# Sheet1.net
KiCad netlist of a schematic drawn in Altium Designer
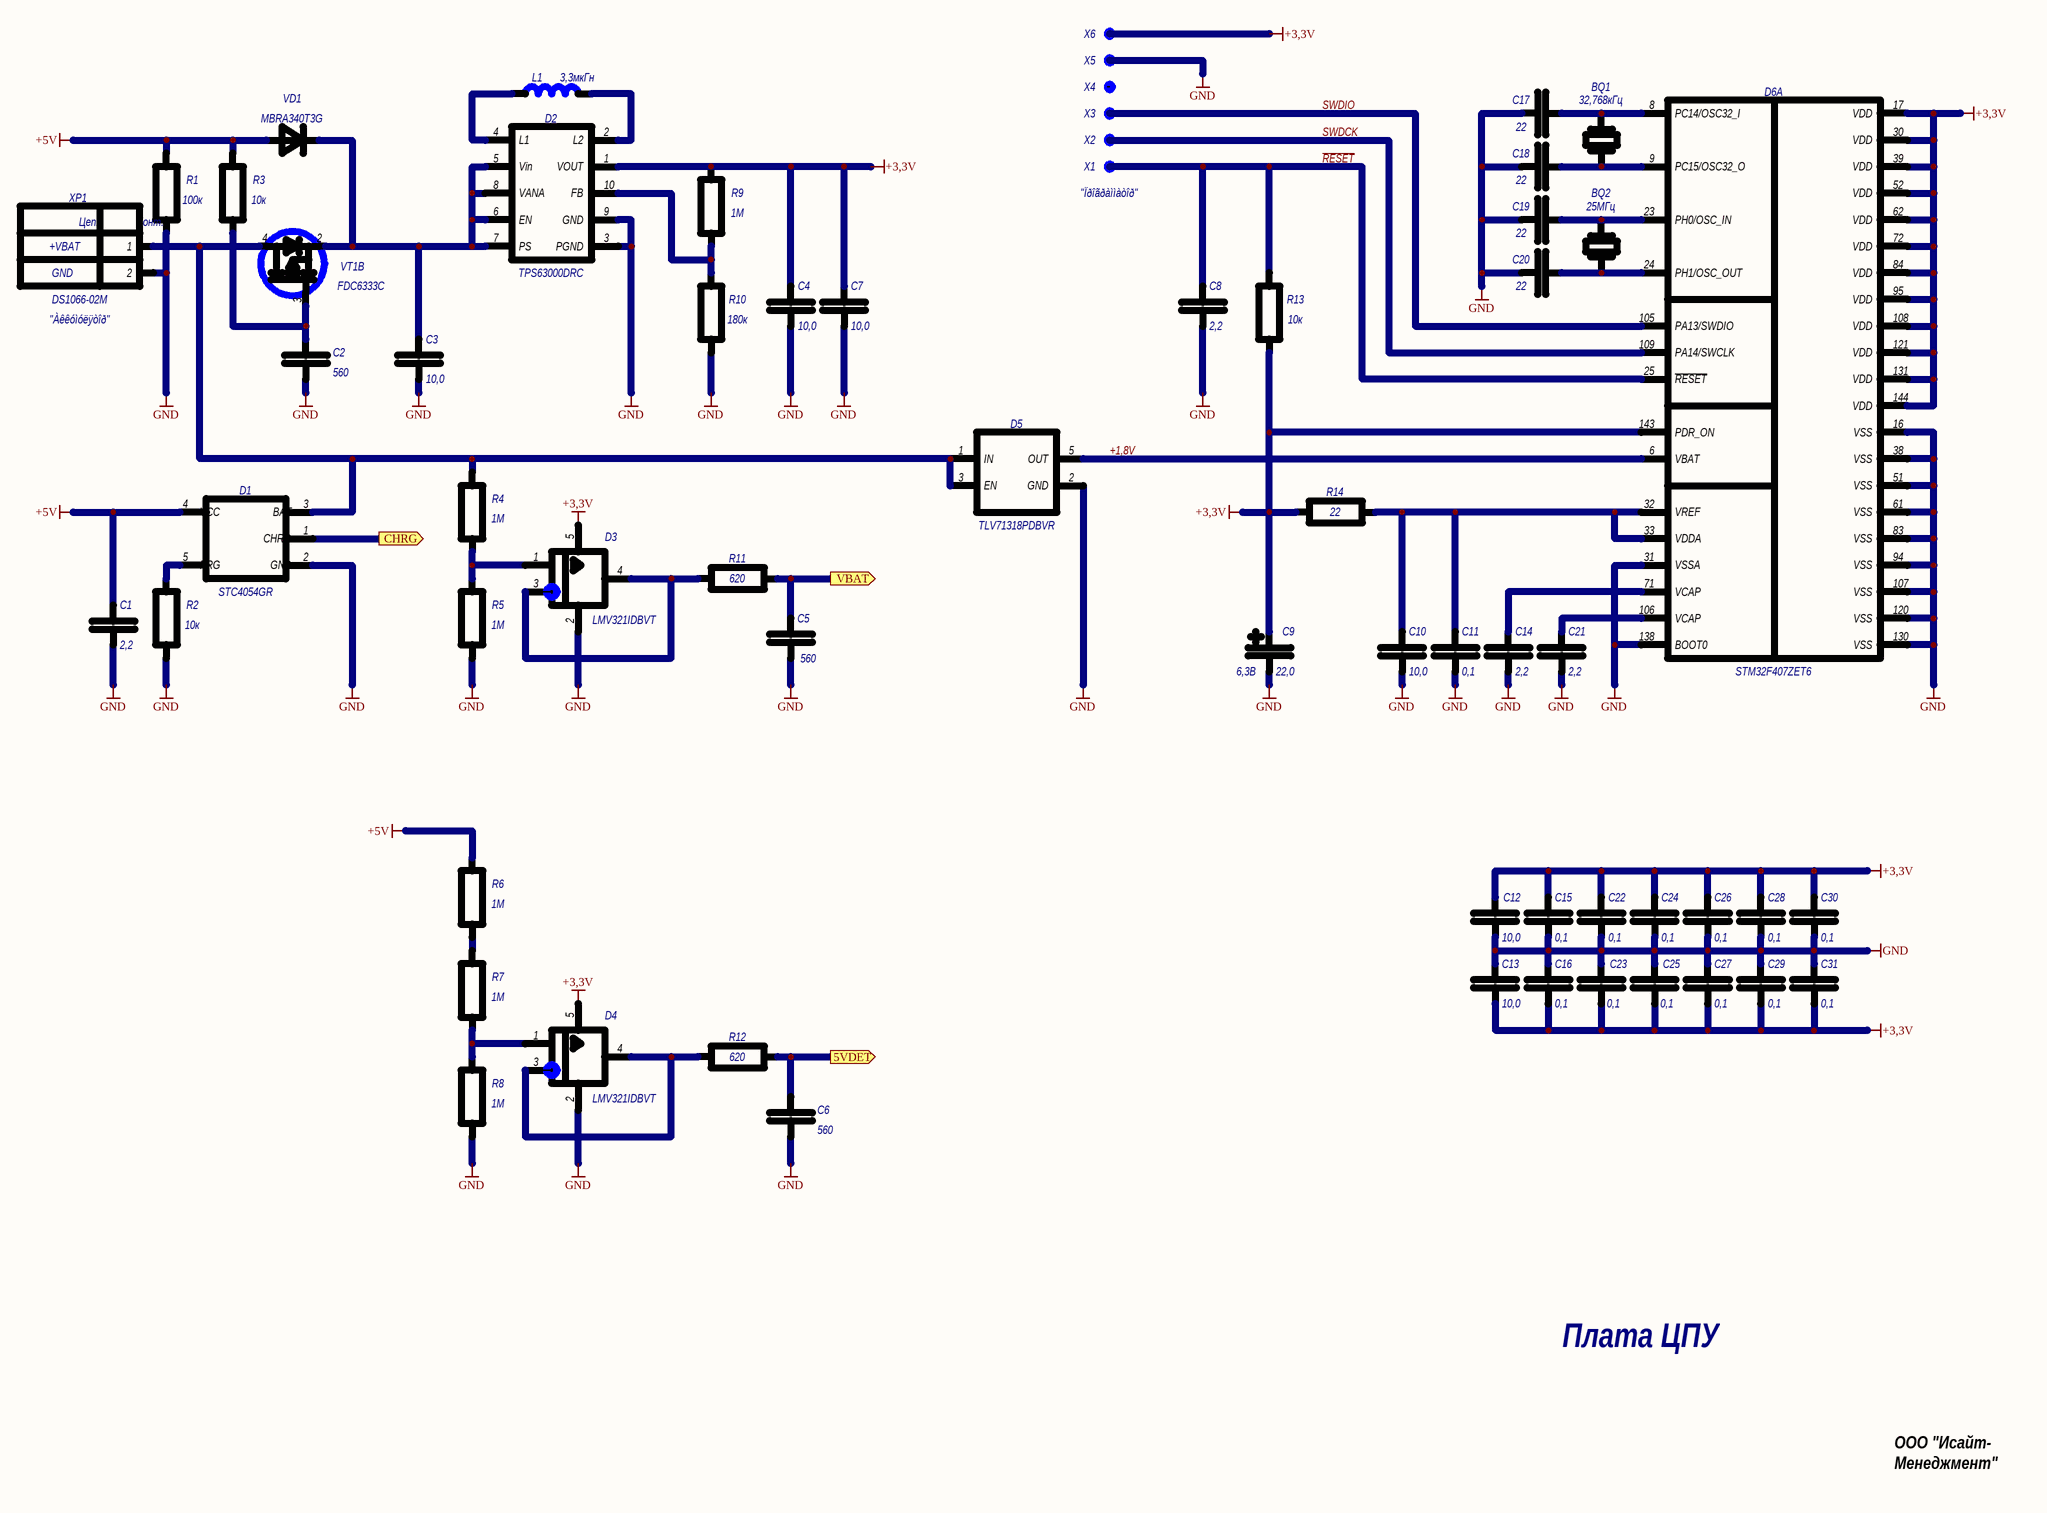
[diagram p0: Sheet1.SCHDOC]

(export (version "E")
  (design (tool "Eeschema 10.0.6"))
  (components
    (comp (ref "BQ1")
      (value "DT38-32K768")
      (footprint "DT38")
      (description "РЕЗОНАТОР")
      (fields (field (name "ALTIUM_UNNAMED_1") "32,768кГц"))
      (libsource (lib "*") (part "DT38-32K768"))
    )
    (comp (ref "BQ2")
      (value "HC49U-06M")
      (footprint "HC49U")
      (description "РЕЗОНАТОР")
      (fields (field (name "ALTIUM_UNNAMED_1") "25МГц"))
      (libsource (lib "*") (part "HC49U-06M"))
    )
    (comp (ref "C1")
      (value "2,2")
      (footprint "0805")
      (description "КОНДЕНСАТОР")
      (fields (field (name "Comment") "К0805"))
      (libsource (lib "*") (part "К0805"))
    )
    (comp (ref "C2")
      (value "560")
      (footprint "0805")
      (description "КОНДЕНСАТОР")
      (fields (field (name "Comment") "К0805"))
      (libsource (lib "*") (part "К0805"))
    )
    (comp (ref "C3")
      (value "10,0")
      (footprint "0805")
      (description "КОНДЕНСАТОР")
      (fields (field (name "Comment") "К0805"))
      (libsource (lib "*") (part "К0805"))
    )
    (comp (ref "C4")
      (value "10,0")
      (footprint "0805")
      (description "КОНДЕНСАТОР")
      (fields (field (name "Comment") "К0805"))
      (libsource (lib "*") (part "К0805"))
    )
    (comp (ref "C5")
      (value "560")
      (footprint "0805")
      (description "КОНДЕНСАТОР")
      (fields (field (name "Comment") "К0805"))
      (libsource (lib "*") (part "К0805"))
    )
    (comp (ref "C6")
      (value "560")
      (footprint "0805")
      (description "КОНДЕНСАТОР")
      (fields (field (name "Comment") "К0805"))
      (libsource (lib "*") (part "К0805"))
    )
    (comp (ref "C7")
      (value "10,0")
      (footprint "0805")
      (description "КОНДЕНСАТОР")
      (fields (field (name "Comment") "К0805"))
      (libsource (lib "*") (part "К0805"))
    )
    (comp (ref "C8")
      (value "2,2")
      (footprint "0805")
      (description "КОНДЕНСАТОР")
      (fields (field (name "Comment") "К0805"))
      (libsource (lib "*") (part "К0805"))
    )
    (comp (ref "C9")
      (value "22,0")
      (footprint "TANTAL")
      (description "КОНДЕНСАТОР")
      (fields (field (name "TG") "6,3В") (field (name "Comment") "КТ"))
      (libsource (lib "*") (part "КТ"))
    )
    (comp (ref "C10")
      (value "10,0")
      (footprint "0805")
      (description "КОНДЕНСАТОР")
      (fields (field (name "Comment") "К0805"))
      (libsource (lib "*") (part "К0805"))
    )
    (comp (ref "C11")
      (value "0,1")
      (footprint "0805")
      (description "КОНДЕНСАТОР")
      (fields (field (name "Comment") "К0805"))
      (libsource (lib "*") (part "К0805"))
    )
    (comp (ref "C12")
      (value "10,0")
      (footprint "0805")
      (description "КОНДЕНСАТОР")
      (fields (field (name "Comment") "К0805"))
      (libsource (lib "*") (part "К0805"))
    )
    (comp (ref "C13")
      (value "10,0")
      (footprint "0805")
      (description "КОНДЕНСАТОР")
      (fields (field (name "Comment") "К0805"))
      (libsource (lib "*") (part "К0805"))
    )
    (comp (ref "C14")
      (value "2,2")
      (footprint "0805")
      (description "КОНДЕНСАТОР")
      (fields (field (name "Comment") "К0805"))
      (libsource (lib "*") (part "К0805"))
    )
    (comp (ref "C15")
      (value "0,1")
      (footprint "0805")
      (description "КОНДЕНСАТОР")
      (fields (field (name "Comment") "К0805"))
      (libsource (lib "*") (part "К0805"))
    )
    (comp (ref "C16")
      (value "0,1")
      (footprint "0805")
      (description "КОНДЕНСАТОР")
      (fields (field (name "Comment") "К0805"))
      (libsource (lib "*") (part "К0805"))
    )
    (comp (ref "C17")
      (value "22")
      (footprint "0805")
      (description "КОНДЕНСАТОР")
      (fields (field (name "Comment") "К0805"))
      (libsource (lib "*") (part "К0805"))
    )
    (comp (ref "C18")
      (value "22")
      (footprint "0805")
      (description "КОНДЕНСАТОР")
      (fields (field (name "Comment") "К0805"))
      (libsource (lib "*") (part "К0805"))
    )
    (comp (ref "C19")
      (value "22")
      (footprint "0805")
      (description "КОНДЕНСАТОР")
      (fields (field (name "Comment") "К0805"))
      (libsource (lib "*") (part "К0805"))
    )
    (comp (ref "C20")
      (value "22")
      (footprint "0805")
      (description "КОНДЕНСАТОР")
      (fields (field (name "Comment") "К0805"))
      (libsource (lib "*") (part "К0805"))
    )
    (comp (ref "C21")
      (value "2,2")
      (footprint "0805")
      (description "КОНДЕНСАТОР")
      (fields (field (name "Comment") "К0805"))
      (libsource (lib "*") (part "К0805"))
    )
    (comp (ref "C22")
      (value "0,1")
      (footprint "0805")
      (description "КОНДЕНСАТОР")
      (fields (field (name "Comment") "К0805"))
      (libsource (lib "*") (part "К0805"))
    )
    (comp (ref "C23")
      (value "0,1")
      (footprint "0805")
      (description "КОНДЕНСАТОР")
      (fields (field (name "Comment") "К0805"))
      (libsource (lib "*") (part "К0805"))
    )
    (comp (ref "C24")
      (value "0,1")
      (footprint "0805")
      (description "КОНДЕНСАТОР")
      (fields (field (name "Comment") "К0805"))
      (libsource (lib "*") (part "К0805"))
    )
    (comp (ref "C25")
      (value "0,1")
      (footprint "0805")
      (description "КОНДЕНСАТОР")
      (fields (field (name "Comment") "К0805"))
      (libsource (lib "*") (part "К0805"))
    )
    (comp (ref "C26")
      (value "0,1")
      (footprint "0805")
      (description "КОНДЕНСАТОР")
      (fields (field (name "Comment") "К0805"))
      (libsource (lib "*") (part "К0805"))
    )
    (comp (ref "C27")
      (value "0,1")
      (footprint "0805")
      (description "КОНДЕНСАТОР")
      (fields (field (name "Comment") "К0805"))
      (libsource (lib "*") (part "К0805"))
    )
    (comp (ref "C28")
      (value "0,1")
      (footprint "0805")
      (description "КОНДЕНСАТОР")
      (fields (field (name "Comment") "К0805"))
      (libsource (lib "*") (part "К0805"))
    )
    (comp (ref "C29")
      (value "0,1")
      (footprint "0805")
      (description "КОНДЕНСАТОР")
      (fields (field (name "Comment") "К0805"))
      (libsource (lib "*") (part "К0805"))
    )
    (comp (ref "C30")
      (value "0,1")
      (footprint "0805")
      (description "КОНДЕНСАТОР")
      (fields (field (name "Comment") "К0805"))
      (libsource (lib "*") (part "К0805"))
    )
    (comp (ref "C31")
      (value "0,1")
      (footprint "0805")
      (description "КОНДЕНСАТОР")
      (fields (field (name "Comment") "К0805"))
      (libsource (lib "*") (part "К0805"))
    )
    (comp (ref "D1")
      (value "STC4054GR")
      (footprint "SOT-23-5")
      (description "{Description}")
      (libsource (lib "*") (part "STC4054GR"))
    )
    (comp (ref "D2")
      (value "TPS63000DRC")
      (footprint "VSON-10")
      (description "{Description}")
      (libsource (lib "*") (part "TPS63000DRC"))
    )
    (comp (ref "D3")
      (value "LMV321IDBVT")
      (footprint "SOT-23-5")
      (description "{Description}")
      (libsource (lib "*") (part "LMV321IDBVT"))
    )
    (comp (ref "D4")
      (value "LMV321IDBVT")
      (footprint "SOT-23-5")
      (description "{Description}")
      (libsource (lib "*") (part "LMV321IDBVT"))
    )
    (comp (ref "D5")
      (value "TLV71318PDBVR")
      (footprint "SOT-23-5")
      (description "{Description}")
      (libsource (lib "*") (part "TLV71318PDBVR"))
    )
    (comp (ref "D6")
      (value "STM32F407ZET6")
      (footprint "LQFP-144")
      (libsource (lib "*") (part "STM32F407ZET6"))
    )
    (comp (ref "L1")
      (value "SRN3015-101M")
      (footprint "SRN3015")
      (description "{Description}")
      (fields (field (name "ALTIUM_UNNAMED_1") "3,3мкГн"))
      (libsource (lib "*") (part "SRN3015-101M"))
    )
    (comp (ref "R1")
      (value "Р0805")
      (footprint "0805")
      (description "РЕЗИСТОР")
      (fields (field (name "ALTIUM_UNNAMED_1") "100к"))
      (libsource (lib "*") (part "Р0805"))
    )
    (comp (ref "R2")
      (value "Р0805")
      (footprint "0805")
      (description "РЕЗИСТОР")
      (fields (field (name "ALTIUM_UNNAMED_1") "10к"))
      (libsource (lib "*") (part "Р0805"))
    )
    (comp (ref "R3")
      (value "Р0805")
      (footprint "0805")
      (description "РЕЗИСТОР")
      (fields (field (name "ALTIUM_UNNAMED_1") "10к"))
      (libsource (lib "*") (part "Р0805"))
    )
    (comp (ref "R4")
      (value "1M")
      (footprint "0805")
      (description "РЕЗИСТОР")
      (fields (field (name "Comment") "Р0805"))
      (libsource (lib "*") (part "Р0805"))
    )
    (comp (ref "R5")
      (value "1M")
      (footprint "0805")
      (description "РЕЗИСТОР")
      (fields (field (name "Comment") "Р0805"))
      (libsource (lib "*") (part "Р0805"))
    )
    (comp (ref "R6")
      (value "1M")
      (footprint "0805")
      (description "РЕЗИСТОР")
      (fields (field (name "Comment") "Р0805"))
      (libsource (lib "*") (part "Р0805"))
    )
    (comp (ref "R7")
      (value "1M")
      (footprint "0805")
      (description "РЕЗИСТОР")
      (fields (field (name "Comment") "Р0805"))
      (libsource (lib "*") (part "Р0805"))
    )
    (comp (ref "R8")
      (value "1M")
      (footprint "0805")
      (description "РЕЗИСТОР")
      (fields (field (name "Comment") "Р0805"))
      (libsource (lib "*") (part "Р0805"))
    )
    (comp (ref "R9")
      (value "1M")
      (footprint "0805")
      (description "РЕЗИСТОР")
      (fields (field (name "Comment") "Р0805"))
      (libsource (lib "") (part "Р0805_1"))
    )
    (comp (ref "R10")
      (value "Р0805")
      (footprint "0805")
      (description "РЕЗИСТОР")
      (fields (field (name "ALTIUM_UNNAMED_1") "180к"))
      (libsource (lib "*") (part "Р0805"))
    )
    (comp (ref "R11")
      (value "620")
      (footprint "0805")
      (description "РЕЗИСТОР")
      (fields (field (name "Comment") "Р0805"))
      (libsource (lib "*") (part "Р0805"))
    )
    (comp (ref "R12")
      (value "620")
      (footprint "0805")
      (description "РЕЗИСТОР")
      (fields (field (name "Comment") "Р0805"))
      (libsource (lib "*") (part "Р0805"))
    )
    (comp (ref "R13")
      (value "Р0805")
      (footprint "0805")
      (description "РЕЗИСТОР")
      (fields (field (name "ALTIUM_UNNAMED_1") "10к"))
      (libsource (lib "*") (part "Р0805"))
    )
    (comp (ref "R14")
      (value "22")
      (footprint "0805")
      (description "РЕЗИСТОР")
      (fields (field (name "Comment") "Р0805"))
      (libsource (lib "*") (part "Р0805"))
    )
    (comp (ref "VD1")
      (value "MBRA340T3G")
      (footprint "SMA")
      (description "{Description}")
      (libsource (lib "*") (part "MBRA340T3G"))
    )
    (comp (ref "VT1")
      (value "FDC6333C")
      (footprint "SOT-23-6")
      (description "{Description}")
      (libsource (lib "*") (part "FDC6333C"))
    )
    (comp (ref "X1") (value "X") (footprint "01") (description "КОНТАКТ") (libsource (lib "*") (part "X")))
    (comp (ref "X2") (value "X") (footprint "01") (description "КОНТАКТ") (libsource (lib "*") (part "X")))
    (comp (ref "X3") (value "X") (footprint "01") (description "КОНТАКТ") (libsource (lib "*") (part "X")))
    (comp (ref "X4") (value "X") (footprint "01") (description "КОНТАКТ") (libsource (lib "*") (part "X")))
    (comp (ref "X5") (value "X") (footprint "01") (description "КОНТАКТ") (libsource (lib "*") (part "X")))
    (comp (ref "X6") (value "X") (footprint "01") (description "КОНТАКТ") (libsource (lib "*") (part "X")))
    (comp (ref "XP1")
      (value "DS1066-02M")
      (footprint "DS1066-02M")
      (description "{Description}")
      (fields (field (name "2") "GND") (field (name "1") "+VBAT"))
      (libsource (lib "*") (part "DS1066-02M"))
    )
  )
  (nets
    (net (code "1") (name "+3,3V") (class "Default")
      (node (ref "C12") (pin "1") (pinfunction "1_1") (pintype "passive"))
      (node (ref "C13") (pin "1") (pinfunction "1_1") (pintype "passive"))
      (node (ref "C15") (pin "2") (pinfunction "2_2") (pintype "passive"))
      (node (ref "C16") (pin "1") (pinfunction "1_1") (pintype "passive"))
      (node (ref "C22") (pin "2") (pinfunction "2_2") (pintype "passive"))
      (node (ref "C23") (pin "2") (pinfunction "2_2") (pintype "passive"))
      (node (ref "C24") (pin "2") (pinfunction "2_2") (pintype "passive"))
      (node (ref "C25") (pin "2") (pinfunction "2_2") (pintype "passive"))
      (node (ref "C26") (pin "2") (pinfunction "2_2") (pintype "passive"))
      (node (ref "C27") (pin "1") (pinfunction "1_1") (pintype "passive"))
      (node (ref "C28") (pin "2") (pinfunction "2_2") (pintype "passive"))
      (node (ref "C29") (pin "1") (pinfunction "1_1") (pintype "passive"))
      (node (ref "C30") (pin "2") (pinfunction "2_2") (pintype "passive"))
      (node (ref "C31") (pin "1") (pinfunction "1_1") (pintype "passive"))
      (node (ref "C4") (pin "2") (pinfunction "2_2") (pintype "passive"))
      (node (ref "C7") (pin "2") (pinfunction "2_2") (pintype "passive"))
      (node (ref "C9") (pin "1") (pinfunction "Plus_1") (pintype "passive"))
      (node (ref "D2") (pin "1") (pinfunction "VOUT_1") (pintype "passive"))
      (node (ref "D3") (pin "5") (pinfunction "V_5") (pintype "passive"))
      (node (ref "D4") (pin "5") (pinfunction "V_5") (pintype "passive"))
      (node (ref "D6") (pin "108") (pinfunction "VDD_108") (pintype "passive"))
      (node (ref "D6") (pin "121") (pinfunction "VDD_121") (pintype "passive"))
      (node (ref "D6") (pin "131") (pinfunction "VDD_131") (pintype "passive"))
      (node (ref "D6") (pin "143") (pinfunction "PDR_ON_143") (pintype "passive"))
      (node (ref "D6") (pin "144") (pinfunction "VDD_144") (pintype "passive"))
      (node (ref "D6") (pin "17") (pinfunction "VDD_17") (pintype "passive"))
      (node (ref "D6") (pin "30") (pinfunction "VDD_30") (pintype "passive"))
      (node (ref "D6") (pin "39") (pinfunction "VDD_39") (pintype "passive"))
      (node (ref "D6") (pin "52") (pinfunction "VDD_52") (pintype "passive"))
      (node (ref "D6") (pin "62") (pinfunction "VDD_62") (pintype "passive"))
      (node (ref "D6") (pin "72") (pinfunction "VDD_72") (pintype "passive"))
      (node (ref "D6") (pin "84") (pinfunction "VDD_84") (pintype "passive"))
      (node (ref "D6") (pin "95") (pinfunction "VDD_95") (pintype "passive"))
      (node (ref "R13") (pin "1") (pinfunction "1_1") (pintype "passive"))
      (node (ref "R14") (pin "2") (pinfunction "2_2") (pintype "passive"))
      (node (ref "R9") (pin "2") (pinfunction "2_2") (pintype "passive"))
      (node (ref "X6") (pin "1") (pinfunction "1_1") (pintype "passive"))
    )
    (net (code "2") (name "+5V") (class "Default")
      (node (ref "C1") (pin "2") (pinfunction "2_2") (pintype "passive"))
      (node (ref "D1") (pin "4") (pinfunction "VCC_4") (pintype "passive"))
      (node (ref "R1") (pin "2") (pinfunction "2_2") (pintype "passive"))
      (node (ref "R3") (pin "2") (pinfunction "2_2") (pintype "passive"))
      (node (ref "R6") (pin "2") (pinfunction "2_2") (pintype "passive"))
      (node (ref "VD1") (pin "A") (pinfunction "Anod_A") (pintype "passive"))
    )
    (net (code "3") (name "/+1,8V") (class "Default")
      (node (ref "D5") (pin "5") (pinfunction "OUT_5") (pintype "passive"))
      (node (ref "D6") (pin "6") (pinfunction "VBAT_6") (pintype "passive"))
    )
    (net (code "4") (name "/5VDET") (class "Default")
      (node (ref "C6") (pin "2") (pinfunction "2_2") (pintype "passive"))
      (node (ref "R12") (pin "1") (pinfunction "1_1") (pintype "passive"))
    )
    (net (code "5") (name "/CHRG") (class "Default")
      (node (ref "D1") (pin "1") (pinfunction "CHRG_1") (pintype "passive"))
    )
    (net (code "6") (name "/SWDCK") (class "Default")
      (node (ref "D6") (pin "109") (pinfunction "PA14/SWCLK_109") (pintype "passive"))
      (node (ref "X2") (pin "1") (pinfunction "1_1") (pintype "passive"))
    )
    (net (code "7") (name "/SWDIO") (class "Default")
      (node (ref "D6") (pin "105") (pinfunction "PA13/SWDIO_105") (pintype "passive"))
      (node (ref "X3") (pin "1") (pinfunction "1_1") (pintype "passive"))
    )
    (net (code "8") (name "/VBAT") (class "Default")
      (node (ref "C5") (pin "1") (pinfunction "1_1") (pintype "passive"))
      (node (ref "R11") (pin "1") (pinfunction "1_1") (pintype "passive"))
    )
    (net (code "9") (name "/~{RESET}") (class "Default")
      (node (ref "C8") (pin "2") (pinfunction "2_2") (pintype "passive"))
      (node (ref "D6") (pin "25") (pinfunction "~{RESET}_25") (pintype "passive"))
      (node (ref "R13") (pin "2") (pinfunction "2_2") (pintype "passive"))
      (node (ref "X1") (pin "1") (pinfunction "1_1") (pintype "passive"))
    )
    (net (code "10") (name "GND") (class "Default")
      (node (ref "C1") (pin "1") (pinfunction "1_1") (pintype "passive"))
      (node (ref "C10") (pin "1") (pinfunction "1_1") (pintype "passive"))
      (node (ref "C11") (pin "1") (pinfunction "1_1") (pintype "passive"))
      (node (ref "C12") (pin "2") (pinfunction "2_2") (pintype "passive"))
      (node (ref "C13") (pin "2") (pinfunction "2_2") (pintype "passive"))
      (node (ref "C14") (pin "1") (pinfunction "1_1") (pintype "passive"))
      (node (ref "C15") (pin "1") (pinfunction "1_1") (pintype "passive"))
      (node (ref "C16") (pin "2") (pinfunction "2_2") (pintype "passive"))
      (node (ref "C17") (pin "2") (pinfunction "2_2") (pintype "passive"))
      (node (ref "C18") (pin "2") (pinfunction "2_2") (pintype "passive"))
      (node (ref "C19") (pin "2") (pinfunction "2_2") (pintype "passive"))
      (node (ref "C2") (pin "1") (pinfunction "1_1") (pintype "passive"))
      (node (ref "C20") (pin "2") (pinfunction "2_2") (pintype "passive"))
      (node (ref "C21") (pin "1") (pinfunction "1_1") (pintype "passive"))
      (node (ref "C22") (pin "1") (pinfunction "1_1") (pintype "passive"))
      (node (ref "C23") (pin "1") (pinfunction "1_1") (pintype "passive"))
      (node (ref "C24") (pin "1") (pinfunction "1_1") (pintype "passive"))
      (node (ref "C25") (pin "1") (pinfunction "1_1") (pintype "passive"))
      (node (ref "C26") (pin "1") (pinfunction "1_1") (pintype "passive"))
      (node (ref "C27") (pin "2") (pinfunction "2_2") (pintype "passive"))
      (node (ref "C28") (pin "1") (pinfunction "1_1") (pintype "passive"))
      (node (ref "C29") (pin "2") (pinfunction "2_2") (pintype "passive"))
      (node (ref "C3") (pin "1") (pinfunction "1_1") (pintype "passive"))
      (node (ref "C30") (pin "1") (pinfunction "1_1") (pintype "passive"))
      (node (ref "C31") (pin "2") (pinfunction "2_2") (pintype "passive"))
      (node (ref "C4") (pin "1") (pinfunction "1_1") (pintype "passive"))
      (node (ref "C5") (pin "2") (pinfunction "2_2") (pintype "passive"))
      (node (ref "C6") (pin "1") (pinfunction "1_1") (pintype "passive"))
      (node (ref "C7") (pin "1") (pinfunction "1_1") (pintype "passive"))
      (node (ref "C8") (pin "1") (pinfunction "1_1") (pintype "passive"))
      (node (ref "C9") (pin "2") (pinfunction "Minus_2") (pintype "passive"))
      (node (ref "D1") (pin "2") (pinfunction "GND_2") (pintype "passive"))
      (node (ref "D2") (pin "11") (pinfunction "GND_11") (pintype "power_in"))
      (node (ref "D2") (pin "3") (pinfunction "PGND_3") (pintype "passive"))
      (node (ref "D2") (pin "9") (pinfunction "GND_9") (pintype "passive"))
      (node (ref "D3") (pin "2") (pinfunction "G_2") (pintype "passive"))
      (node (ref "D4") (pin "2") (pinfunction "G_2") (pintype "passive"))
      (node (ref "D5") (pin "2") (pinfunction "GND_2") (pintype "passive"))
      (node (ref "D6") (pin "107") (pinfunction "VSS_107") (pintype "passive"))
      (node (ref "D6") (pin "120") (pinfunction "VSS_120") (pintype "passive"))
      (node (ref "D6") (pin "130") (pinfunction "VSS_130") (pintype "passive"))
      (node (ref "D6") (pin "138") (pinfunction "BOOT0_138") (pintype "passive"))
      (node (ref "D6") (pin "16") (pinfunction "VSS_16") (pintype "passive"))
      (node (ref "D6") (pin "31") (pinfunction "VSSA_31") (pintype "passive"))
      (node (ref "D6") (pin "38") (pinfunction "VSS_38") (pintype "passive"))
      (node (ref "D6") (pin "51") (pinfunction "VSS_51") (pintype "passive"))
      (node (ref "D6") (pin "61") (pinfunction "VSS_61") (pintype "passive"))
      (node (ref "D6") (pin "83") (pinfunction "VSS_83") (pintype "passive"))
      (node (ref "D6") (pin "94") (pinfunction "VSS_94") (pintype "passive"))
      (node (ref "R1") (pin "1") (pinfunction "1_1") (pintype "passive"))
      (node (ref "R10") (pin "1") (pinfunction "1_1") (pintype "passive"))
      (node (ref "R2") (pin "1") (pinfunction "1_1") (pintype "passive"))
      (node (ref "R5") (pin "1") (pinfunction "1_1") (pintype "passive"))
      (node (ref "R8") (pin "1") (pinfunction "1_1") (pintype "passive"))
      (node (ref "X5") (pin "1") (pinfunction "1_1") (pintype "passive"))
      (node (ref "XP1") (pin "2") (pinfunction "2_2") (pintype "passive"))
    )
    (net (code "11") (name "Net-(C14-Pad2)") (class "Default")
      (node (ref "C14") (pin "2") (pinfunction "2_2") (pintype "passive"))
      (node (ref "D6") (pin "71") (pinfunction "VCAP_71") (pintype "passive"))
    )
    (net (code "12") (name "Net-(C21-Pad2)") (class "Default")
      (node (ref "C21") (pin "2") (pinfunction "2_2") (pintype "passive"))
      (node (ref "D6") (pin "106") (pinfunction "VCAP_106") (pintype "passive"))
    )
    (net (code "13") (name "Net-(D1-BAT)") (class "Default")
      (node (ref "D1") (pin "3") (pinfunction "BAT_3") (pintype "passive"))
      (node (ref "D5") (pin "1") (pinfunction "IN_1") (pintype "passive"))
      (node (ref "D5") (pin "3") (pinfunction "EN_3") (pintype "passive"))
      (node (ref "R4") (pin "2") (pinfunction "2_2") (pintype "passive"))
      (node (ref "VT1") (pin "4") (pinfunction "Drain_4") (pintype "passive"))
      (node (ref "XP1") (pin "1") (pinfunction "1_1") (pintype "passive"))
    )
    (net (code "14") (name "Net-(D1-PRG)") (class "Default")
      (node (ref "D1") (pin "5") (pinfunction "PRG_5") (pintype "passive"))
      (node (ref "R2") (pin "2") (pinfunction "2_2") (pintype "passive"))
    )
    (net (code "15") (name "Net-(D2-EN)") (class "Default")
      (node (ref "C3") (pin "2") (pinfunction "2_2") (pintype "passive"))
      (node (ref "D2") (pin "5") (pinfunction "Vin_5") (pintype "passive"))
      (node (ref "D2") (pin "6") (pinfunction "EN_6") (pintype "passive"))
      (node (ref "D2") (pin "7") (pinfunction "PS_7") (pintype "passive"))
      (node (ref "D2") (pin "8") (pinfunction "VANA_8") (pintype "passive"))
      (node (ref "VD1") (pin "K") (pinfunction "Katod_K") (pintype "passive"))
      (node (ref "VT1") (pin "2") (pinfunction "Source_2") (pintype "passive"))
    )
    (net (code "16") (name "Net-(D2-FB)") (class "Default")
      (node (ref "D2") (pin "10") (pinfunction "FB_10") (pintype "passive"))
      (node (ref "R10") (pin "2") (pinfunction "2_2") (pintype "passive"))
      (node (ref "R9") (pin "1") (pinfunction "1_1") (pintype "passive"))
    )
    (net (code "17") (name "Net-(D2-L1)") (class "Default")
      (node (ref "D2") (pin "4") (pinfunction "L1_4") (pintype "passive"))
      (node (ref "L1") (pin "1") (pinfunction "1_1") (pintype "passive"))
    )
    (net (code "18") (name "Net-(D2-L2)") (class "Default")
      (node (ref "D2") (pin "2") (pinfunction "L2_2") (pintype "passive"))
      (node (ref "L1") (pin "2") (pinfunction "2_2") (pintype "passive"))
    )
    (net (code "19") (name "Net-(D3-+IN)") (class "Default")
      (node (ref "D3") (pin "1") (pinfunction "+IN_1") (pintype "passive"))
      (node (ref "R4") (pin "1") (pinfunction "1_1") (pintype "passive"))
      (node (ref "R5") (pin "2") (pinfunction "2_2") (pintype "passive"))
    )
    (net (code "20") (name "Net-(D3--IN)") (class "Default")
      (node (ref "D3") (pin "3") (pinfunction "-IN_3") (pintype "passive"))
      (node (ref "D3") (pin "4") (pinfunction "OUT_4") (pintype "passive"))
      (node (ref "R11") (pin "2") (pinfunction "2_2") (pintype "passive"))
    )
    (net (code "21") (name "Net-(D4-+IN)") (class "Default")
      (node (ref "D4") (pin "1") (pinfunction "+IN_1") (pintype "passive"))
      (node (ref "R7") (pin "2") (pinfunction "2_2") (pintype "passive"))
      (node (ref "R8") (pin "2") (pinfunction "2_2") (pintype "passive"))
    )
    (net (code "22") (name "Net-(D4--IN)") (class "Default")
      (node (ref "D4") (pin "3") (pinfunction "-IN_3") (pintype "passive"))
      (node (ref "D4") (pin "4") (pinfunction "OUT_4") (pintype "passive"))
      (node (ref "R12") (pin "2") (pinfunction "2_2") (pintype "passive"))
    )
    (net (code "23") (name "Net-(D6A-PC14{slash}OSC32_I)") (class "Default")
      (node (ref "BQ1") (pin "2") (pinfunction "2_2") (pintype "passive"))
      (node (ref "C17") (pin "1") (pinfunction "1_1") (pintype "passive"))
      (node (ref "D6") (pin "8") (pinfunction "PC14/OSC32_I_8") (pintype "passive"))
    )
    (net (code "24") (name "Net-(D6A-PC15{slash}OSC32_O)") (class "Default")
      (node (ref "BQ1") (pin "1") (pinfunction "1_1") (pintype "passive"))
      (node (ref "C18") (pin "1") (pinfunction "1_1") (pintype "passive"))
      (node (ref "D6") (pin "9") (pinfunction "PC15/OSC32_O_9") (pintype "passive"))
    )
    (net (code "25") (name "Net-(D6A-PH0{slash}OSC_IN)") (class "Default")
      (node (ref "BQ2") (pin "2") (pinfunction "2_2") (pintype "passive"))
      (node (ref "C19") (pin "1") (pinfunction "1_1") (pintype "passive"))
      (node (ref "D6") (pin "23") (pinfunction "PH0/OSC_IN_23") (pintype "passive"))
    )
    (net (code "26") (name "Net-(D6A-PH1{slash}OSC_OUT)") (class "Default")
      (node (ref "BQ2") (pin "1") (pinfunction "1_1") (pintype "passive"))
      (node (ref "C20") (pin "1") (pinfunction "1_1") (pintype "passive"))
      (node (ref "D6") (pin "24") (pinfunction "PH1/OSC_OUT_24") (pintype "passive"))
    )
    (net (code "27") (name "Net-(D6A-VDDA)") (class "Default")
      (node (ref "C10") (pin "2") (pinfunction "2_2") (pintype "passive"))
      (node (ref "C11") (pin "2") (pinfunction "2_2") (pintype "passive"))
      (node (ref "D6") (pin "32") (pinfunction "VREF_32") (pintype "passive"))
      (node (ref "D6") (pin "33") (pinfunction "VDDA_33") (pintype "passive"))
      (node (ref "R14") (pin "1") (pinfunction "1_1") (pintype "passive"))
    )
    (net (code "28") (name "Net-(R6-Pad1)") (class "Default")
      (node (ref "R6") (pin "1") (pinfunction "1_1") (pintype "passive"))
      (node (ref "R7") (pin "1") (pinfunction "1_1") (pintype "passive"))
    )
    (net (code "29") (name "Net-(VT1B-Gate)") (class "Default")
      (node (ref "C2") (pin "2") (pinfunction "2_2") (pintype "passive"))
      (node (ref "R3") (pin "1") (pinfunction "1_1") (pintype "passive"))
      (node (ref "VT1") (pin "3") (pinfunction "Gate_3") (pintype "passive"))
    )
    (net (code "30") (name "unconnected-(D5-Pad4)") (class "Default")
      (node (ref "D5") (pin "4") (pintype "passive"))
    )
    (net (code "31") (name "unconnected-(D6-Pad49)") (class "Default")
      (node (ref "D6") (pin "49") (pintype "passive"))
    )
    (net (code "32") (name "unconnected-(X4-Pad1)") (class "Default")
      (node (ref "X4") (pin "1") (pinfunction "1_1") (pintype "passive"))
    )
  )
)
